# control_pad_v1-1-0x.net
KiCad netlist of a schematic drawn in EAGLE
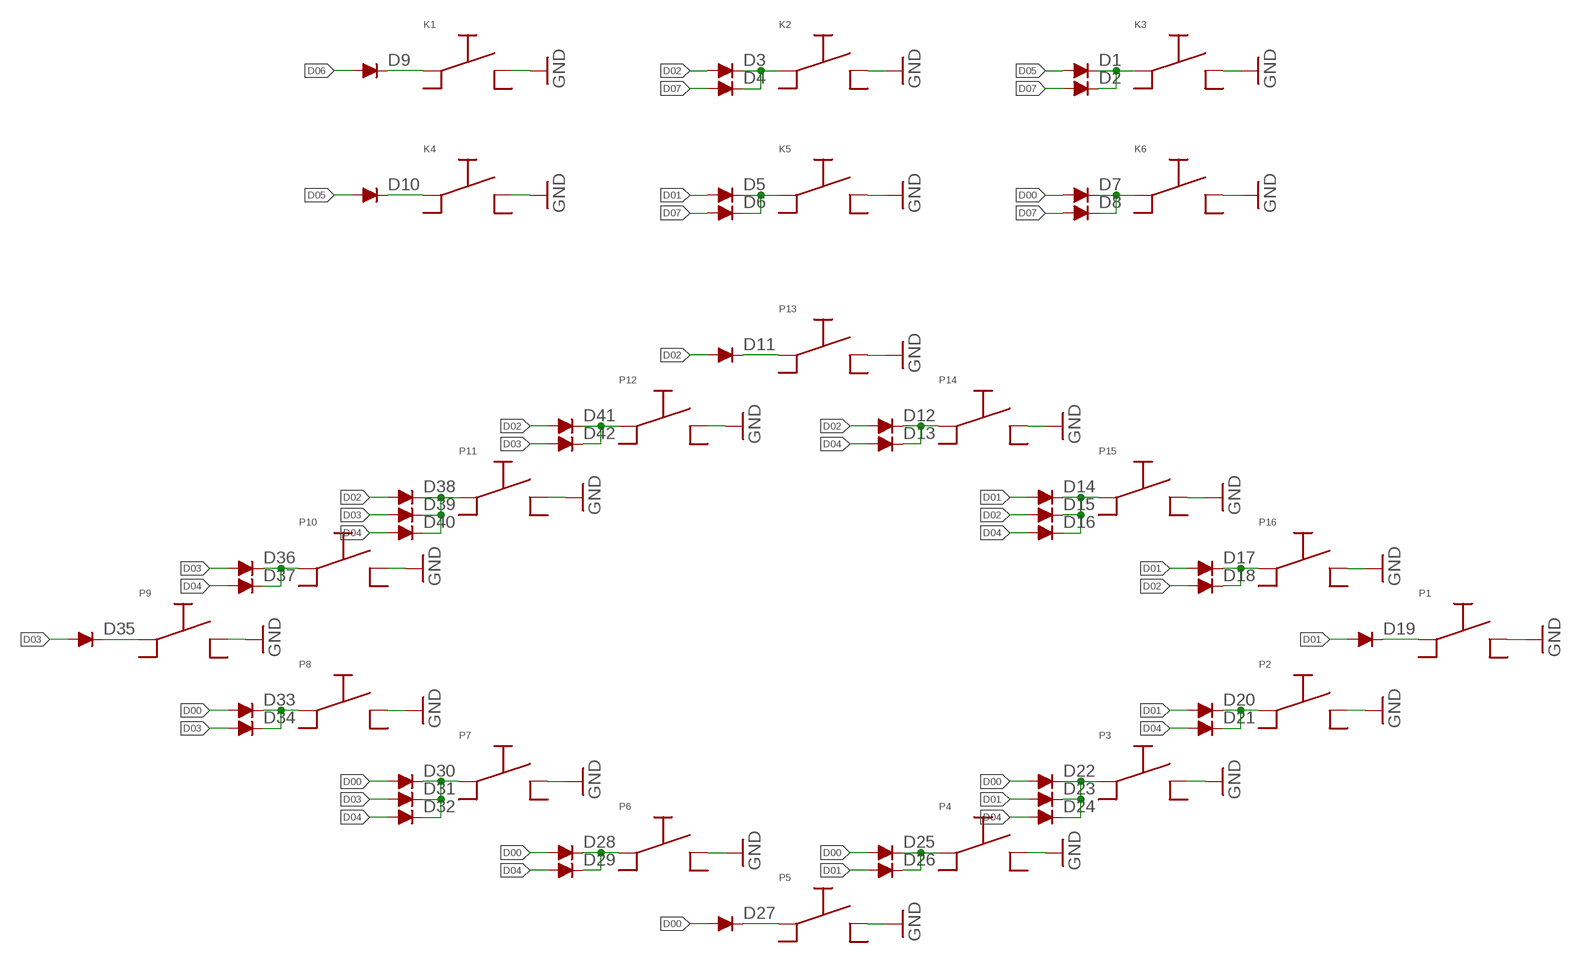
[diagram p0: schematic, sheet 1]

(export (version "E")
  (design (tool "Eeschema 10.0.6"))
  (components
    (comp (ref "D1")
      (value "1N4148")
      (footprint "eagle-import:DO35-10")
      (libsource (lib "eagle-import") (part "1N4148"))
    )
    (comp (ref "D2")
      (value "1N4148")
      (footprint "eagle-import:DO35-10")
      (libsource (lib "eagle-import") (part "1N4148"))
    )
    (comp (ref "D3")
      (value "1N4148")
      (footprint "eagle-import:DO35-10")
      (libsource (lib "eagle-import") (part "1N4148"))
    )
    (comp (ref "D4")
      (value "1N4148")
      (footprint "eagle-import:DO35-10")
      (libsource (lib "eagle-import") (part "1N4148"))
    )
    (comp (ref "D5")
      (value "1N4148")
      (footprint "eagle-import:DO35-10")
      (libsource (lib "eagle-import") (part "1N4148"))
    )
    (comp (ref "D6")
      (value "1N4148")
      (footprint "eagle-import:DO35-10")
      (libsource (lib "eagle-import") (part "1N4148"))
    )
    (comp (ref "D7")
      (value "1N4148")
      (footprint "eagle-import:DO35-10")
      (libsource (lib "eagle-import") (part "1N4148"))
    )
    (comp (ref "D8")
      (value "1N4148")
      (footprint "eagle-import:DO35-10")
      (libsource (lib "eagle-import") (part "1N4148"))
    )
    (comp (ref "D9")
      (value "1N4148")
      (footprint "eagle-import:DO35-10")
      (libsource (lib "eagle-import") (part "1N4148"))
    )
    (comp (ref "D10")
      (value "1N4148")
      (footprint "eagle-import:DO35-10")
      (libsource (lib "eagle-import") (part "1N4148"))
    )
    (comp (ref "D11")
      (value "1N4148")
      (footprint "eagle-import:DO35-10")
      (libsource (lib "eagle-import") (part "1N4148"))
    )
    (comp (ref "D12")
      (value "1N4148")
      (footprint "eagle-import:DO35-10")
      (libsource (lib "eagle-import") (part "1N4148"))
    )
    (comp (ref "D13")
      (value "1N4148")
      (footprint "eagle-import:DO35-10")
      (libsource (lib "eagle-import") (part "1N4148"))
    )
    (comp (ref "D14")
      (value "1N4148")
      (footprint "eagle-import:DO35-10")
      (libsource (lib "eagle-import") (part "1N4148"))
    )
    (comp (ref "D15")
      (value "1N4148")
      (footprint "eagle-import:DO35-10")
      (libsource (lib "eagle-import") (part "1N4148"))
    )
    (comp (ref "D16")
      (value "1N4148")
      (footprint "eagle-import:DO35-10")
      (libsource (lib "eagle-import") (part "1N4148"))
    )
    (comp (ref "D17")
      (value "1N4148")
      (footprint "eagle-import:DO35-10")
      (libsource (lib "eagle-import") (part "1N4148"))
    )
    (comp (ref "D18")
      (value "1N4148")
      (footprint "eagle-import:DO35-10")
      (libsource (lib "eagle-import") (part "1N4148"))
    )
    (comp (ref "D19")
      (value "1N4148")
      (footprint "eagle-import:DO35-10")
      (libsource (lib "eagle-import") (part "1N4148"))
    )
    (comp (ref "D20")
      (value "1N4148")
      (footprint "eagle-import:DO35-10")
      (libsource (lib "eagle-import") (part "1N4148"))
    )
    (comp (ref "D21")
      (value "1N4148")
      (footprint "eagle-import:DO35-10")
      (libsource (lib "eagle-import") (part "1N4148"))
    )
    (comp (ref "D22")
      (value "1N4148")
      (footprint "eagle-import:DO35-10")
      (libsource (lib "eagle-import") (part "1N4148"))
    )
    (comp (ref "D23")
      (value "1N4148")
      (footprint "eagle-import:DO35-10")
      (libsource (lib "eagle-import") (part "1N4148"))
    )
    (comp (ref "D24")
      (value "1N4148")
      (footprint "eagle-import:DO35-10")
      (libsource (lib "eagle-import") (part "1N4148"))
    )
    (comp (ref "D25")
      (value "1N4148")
      (footprint "eagle-import:DO35-10")
      (libsource (lib "eagle-import") (part "1N4148"))
    )
    (comp (ref "D26")
      (value "1N4148")
      (footprint "eagle-import:DO35-10")
      (libsource (lib "eagle-import") (part "1N4148"))
    )
    (comp (ref "D27")
      (value "1N4148")
      (footprint "eagle-import:DO35-10")
      (libsource (lib "eagle-import") (part "1N4148"))
    )
    (comp (ref "D28")
      (value "1N4148")
      (footprint "eagle-import:DO35-10")
      (libsource (lib "eagle-import") (part "1N4148"))
    )
    (comp (ref "D29")
      (value "1N4148")
      (footprint "eagle-import:DO35-10")
      (libsource (lib "eagle-import") (part "1N4148"))
    )
    (comp (ref "D30")
      (value "1N4148")
      (footprint "eagle-import:DO35-10")
      (libsource (lib "eagle-import") (part "1N4148"))
    )
    (comp (ref "D31")
      (value "1N4148")
      (footprint "eagle-import:DO35-10")
      (libsource (lib "eagle-import") (part "1N4148"))
    )
    (comp (ref "D32")
      (value "1N4148")
      (footprint "eagle-import:DO35-10")
      (libsource (lib "eagle-import") (part "1N4148"))
    )
    (comp (ref "D33")
      (value "1N4148")
      (footprint "eagle-import:DO35-10")
      (libsource (lib "eagle-import") (part "1N4148"))
    )
    (comp (ref "D34")
      (value "1N4148")
      (footprint "eagle-import:DO35-10")
      (libsource (lib "eagle-import") (part "1N4148"))
    )
    (comp (ref "D35")
      (value "1N4148")
      (footprint "eagle-import:DO35-10")
      (libsource (lib "eagle-import") (part "1N4148"))
    )
    (comp (ref "D36")
      (value "1N4148")
      (footprint "eagle-import:DO35-10")
      (libsource (lib "eagle-import") (part "1N4148"))
    )
    (comp (ref "D37")
      (value "1N4148")
      (footprint "eagle-import:DO35-10")
      (libsource (lib "eagle-import") (part "1N4148"))
    )
    (comp (ref "D38")
      (value "1N4148")
      (footprint "eagle-import:DO35-10")
      (libsource (lib "eagle-import") (part "1N4148"))
    )
    (comp (ref "D39")
      (value "1N4148")
      (footprint "eagle-import:DO35-10")
      (libsource (lib "eagle-import") (part "1N4148"))
    )
    (comp (ref "D40")
      (value "1N4148")
      (footprint "eagle-import:DO35-10")
      (libsource (lib "eagle-import") (part "1N4148"))
    )
    (comp (ref "D41")
      (value "1N4148")
      (footprint "eagle-import:DO35-10")
      (libsource (lib "eagle-import") (part "1N4148"))
    )
    (comp (ref "D42")
      (value "1N4148")
      (footprint "eagle-import:DO35-10")
      (libsource (lib "eagle-import") (part "1N4148"))
    )
    (comp (ref "K1")
      (value "TACT-SPST")
      (footprint "eagle-import:TACT-SPST")
      (libsource (lib "eagle-import") (part "TACT-SPST"))
    )
    (comp (ref "K2")
      (value "TACT-SPST")
      (footprint "eagle-import:TACT-SPST")
      (libsource (lib "eagle-import") (part "TACT-SPST"))
    )
    (comp (ref "K3")
      (value "TACT-SPST")
      (footprint "eagle-import:TACT-SPST")
      (libsource (lib "eagle-import") (part "TACT-SPST"))
    )
    (comp (ref "K4")
      (value "TACT-SPST")
      (footprint "eagle-import:TACT-SPST")
      (libsource (lib "eagle-import") (part "TACT-SPST"))
    )
    (comp (ref "K5")
      (value "TACT-SPST")
      (footprint "eagle-import:TACT-SPST")
      (libsource (lib "eagle-import") (part "TACT-SPST"))
    )
    (comp (ref "K6")
      (value "TACT-SPST")
      (footprint "eagle-import:TACT-SPST")
      (libsource (lib "eagle-import") (part "TACT-SPST"))
    )
    (comp (ref "P1")
      (value "TACT-SPST")
      (footprint "eagle-import:TACT-SPST")
      (libsource (lib "eagle-import") (part "TACT-SPST"))
    )
    (comp (ref "P2")
      (value "TACT-SPST")
      (footprint "eagle-import:TACT-SPST")
      (libsource (lib "eagle-import") (part "TACT-SPST"))
    )
    (comp (ref "P3")
      (value "TACT-SPST")
      (footprint "eagle-import:TACT-SPST")
      (libsource (lib "eagle-import") (part "TACT-SPST"))
    )
    (comp (ref "P4")
      (value "TACT-SPST")
      (footprint "eagle-import:TACT-SPST")
      (libsource (lib "eagle-import") (part "TACT-SPST"))
    )
    (comp (ref "P5")
      (value "TACT-SPST")
      (footprint "eagle-import:TACT-SPST")
      (libsource (lib "eagle-import") (part "TACT-SPST"))
    )
    (comp (ref "P6")
      (value "TACT-SPST")
      (footprint "eagle-import:TACT-SPST")
      (libsource (lib "eagle-import") (part "TACT-SPST"))
    )
    (comp (ref "P7")
      (value "TACT-SPST")
      (footprint "eagle-import:TACT-SPST")
      (libsource (lib "eagle-import") (part "TACT-SPST"))
    )
    (comp (ref "P8")
      (value "TACT-SPST")
      (footprint "eagle-import:TACT-SPST")
      (libsource (lib "eagle-import") (part "TACT-SPST"))
    )
    (comp (ref "P9")
      (value "TACT-SPST")
      (footprint "eagle-import:TACT-SPST")
      (libsource (lib "eagle-import") (part "TACT-SPST"))
    )
    (comp (ref "P10")
      (value "TACT-SPST")
      (footprint "eagle-import:TACT-SPST")
      (libsource (lib "eagle-import") (part "TACT-SPST"))
    )
    (comp (ref "P11")
      (value "TACT-SPST")
      (footprint "eagle-import:TACT-SPST")
      (libsource (lib "eagle-import") (part "TACT-SPST"))
    )
    (comp (ref "P12")
      (value "TACT-SPST")
      (footprint "eagle-import:TACT-SPST")
      (libsource (lib "eagle-import") (part "TACT-SPST"))
    )
    (comp (ref "P13")
      (value "TACT-SPST")
      (footprint "eagle-import:TACT-SPST")
      (libsource (lib "eagle-import") (part "TACT-SPST"))
    )
    (comp (ref "P14")
      (value "TACT-SPST")
      (footprint "eagle-import:TACT-SPST")
      (libsource (lib "eagle-import") (part "TACT-SPST"))
    )
    (comp (ref "P15")
      (value "TACT-SPST")
      (footprint "eagle-import:TACT-SPST")
      (libsource (lib "eagle-import") (part "TACT-SPST"))
    )
    (comp (ref "P16")
      (value "TACT-SPST")
      (footprint "eagle-import:TACT-SPST")
      (libsource (lib "eagle-import") (part "TACT-SPST"))
    )
  )
  (nets
    (net (code "1") (name "D00") (class "Default")
      (node (ref "D22") (pin "A") (pinfunction "A_A") (pintype "passive"))
      (node (ref "D25") (pin "A") (pinfunction "A_A") (pintype "passive"))
      (node (ref "D27") (pin "A") (pinfunction "A_A") (pintype "passive"))
      (node (ref "D28") (pin "A") (pinfunction "A_A") (pintype "passive"))
      (node (ref "D30") (pin "A") (pinfunction "A_A") (pintype "passive"))
      (node (ref "D33") (pin "A") (pinfunction "A_A") (pintype "passive"))
      (node (ref "D7") (pin "A") (pinfunction "A_A") (pintype "passive"))
    )
    (net (code "2") (name "D01") (class "Default")
      (node (ref "D14") (pin "A") (pinfunction "A_A") (pintype "passive"))
      (node (ref "D17") (pin "A") (pinfunction "A_A") (pintype "passive"))
      (node (ref "D19") (pin "A") (pinfunction "A_A") (pintype "passive"))
      (node (ref "D20") (pin "A") (pinfunction "A_A") (pintype "passive"))
      (node (ref "D23") (pin "A") (pinfunction "A_A") (pintype "passive"))
      (node (ref "D26") (pin "A") (pinfunction "A_A") (pintype "passive"))
      (node (ref "D5") (pin "A") (pinfunction "A_A") (pintype "passive"))
    )
    (net (code "3") (name "D02") (class "Default")
      (node (ref "D11") (pin "A") (pinfunction "A_A") (pintype "passive"))
      (node (ref "D12") (pin "A") (pinfunction "A_A") (pintype "passive"))
      (node (ref "D15") (pin "A") (pinfunction "A_A") (pintype "passive"))
      (node (ref "D18") (pin "A") (pinfunction "A_A") (pintype "passive"))
      (node (ref "D3") (pin "A") (pinfunction "A_A") (pintype "passive"))
      (node (ref "D38") (pin "A") (pinfunction "A_A") (pintype "passive"))
      (node (ref "D41") (pin "A") (pinfunction "A_A") (pintype "passive"))
    )
    (net (code "4") (name "D03") (class "Default")
      (node (ref "D31") (pin "A") (pinfunction "A_A") (pintype "passive"))
      (node (ref "D34") (pin "A") (pinfunction "A_A") (pintype "passive"))
      (node (ref "D35") (pin "A") (pinfunction "A_A") (pintype "passive"))
      (node (ref "D36") (pin "A") (pinfunction "A_A") (pintype "passive"))
      (node (ref "D39") (pin "A") (pinfunction "A_A") (pintype "passive"))
      (node (ref "D42") (pin "A") (pinfunction "A_A") (pintype "passive"))
    )
    (net (code "5") (name "D04") (class "Default")
      (node (ref "D13") (pin "A") (pinfunction "A_A") (pintype "passive"))
      (node (ref "D16") (pin "A") (pinfunction "A_A") (pintype "passive"))
      (node (ref "D21") (pin "A") (pinfunction "A_A") (pintype "passive"))
      (node (ref "D24") (pin "A") (pinfunction "A_A") (pintype "passive"))
      (node (ref "D29") (pin "A") (pinfunction "A_A") (pintype "passive"))
      (node (ref "D32") (pin "A") (pinfunction "A_A") (pintype "passive"))
      (node (ref "D37") (pin "A") (pinfunction "A_A") (pintype "passive"))
      (node (ref "D40") (pin "A") (pinfunction "A_A") (pintype "passive"))
    )
    (net (code "6") (name "D05") (class "Default")
      (node (ref "D1") (pin "A") (pinfunction "A_A") (pintype "passive"))
      (node (ref "D10") (pin "A") (pinfunction "A_A") (pintype "passive"))
    )
    (net (code "7") (name "D06") (class "Default")
      (node (ref "D9") (pin "A") (pinfunction "A_A") (pintype "passive"))
    )
    (net (code "8") (name "D07") (class "Default")
      (node (ref "D2") (pin "A") (pinfunction "A_A") (pintype "passive"))
      (node (ref "D4") (pin "A") (pinfunction "A_A") (pintype "passive"))
      (node (ref "D6") (pin "A") (pinfunction "A_A") (pintype "passive"))
      (node (ref "D8") (pin "A") (pinfunction "A_A") (pintype "passive"))
    )
    (net (code "9") (name "GND") (class "Default")
      (node (ref "K1") (pin "P$2") (pinfunction "P$2_P$2") (pintype "bidirectional"))
      (node (ref "K1") (pin "P$4") (pinfunction "P$2_P$4") (pintype "bidirectional"))
      (node (ref "K2") (pin "P$2") (pinfunction "P$2_P$2") (pintype "bidirectional"))
      (node (ref "K2") (pin "P$4") (pinfunction "P$2_P$4") (pintype "bidirectional"))
      (node (ref "K3") (pin "P$2") (pinfunction "P$2_P$2") (pintype "bidirectional"))
      (node (ref "K3") (pin "P$4") (pinfunction "P$2_P$4") (pintype "bidirectional"))
      (node (ref "K4") (pin "P$2") (pinfunction "P$2_P$2") (pintype "bidirectional"))
      (node (ref "K4") (pin "P$4") (pinfunction "P$2_P$4") (pintype "bidirectional"))
      (node (ref "K5") (pin "P$2") (pinfunction "P$2_P$2") (pintype "bidirectional"))
      (node (ref "K5") (pin "P$4") (pinfunction "P$2_P$4") (pintype "bidirectional"))
      (node (ref "K6") (pin "P$2") (pinfunction "P$2_P$2") (pintype "bidirectional"))
      (node (ref "K6") (pin "P$4") (pinfunction "P$2_P$4") (pintype "bidirectional"))
      (node (ref "P1") (pin "P$2") (pinfunction "P$2_P$2") (pintype "bidirectional"))
      (node (ref "P1") (pin "P$4") (pinfunction "P$2_P$4") (pintype "bidirectional"))
      (node (ref "P10") (pin "P$2") (pinfunction "P$2_P$2") (pintype "bidirectional"))
      (node (ref "P10") (pin "P$4") (pinfunction "P$2_P$4") (pintype "bidirectional"))
      (node (ref "P11") (pin "P$2") (pinfunction "P$2_P$2") (pintype "bidirectional"))
      (node (ref "P11") (pin "P$4") (pinfunction "P$2_P$4") (pintype "bidirectional"))
      (node (ref "P12") (pin "P$2") (pinfunction "P$2_P$2") (pintype "bidirectional"))
      (node (ref "P12") (pin "P$4") (pinfunction "P$2_P$4") (pintype "bidirectional"))
      (node (ref "P13") (pin "P$2") (pinfunction "P$2_P$2") (pintype "bidirectional"))
      (node (ref "P13") (pin "P$4") (pinfunction "P$2_P$4") (pintype "bidirectional"))
      (node (ref "P14") (pin "P$2") (pinfunction "P$2_P$2") (pintype "bidirectional"))
      (node (ref "P14") (pin "P$4") (pinfunction "P$2_P$4") (pintype "bidirectional"))
      (node (ref "P15") (pin "P$2") (pinfunction "P$2_P$2") (pintype "bidirectional"))
      (node (ref "P15") (pin "P$4") (pinfunction "P$2_P$4") (pintype "bidirectional"))
      (node (ref "P16") (pin "P$2") (pinfunction "P$2_P$2") (pintype "bidirectional"))
      (node (ref "P16") (pin "P$4") (pinfunction "P$2_P$4") (pintype "bidirectional"))
      (node (ref "P2") (pin "P$2") (pinfunction "P$2_P$2") (pintype "bidirectional"))
      (node (ref "P2") (pin "P$4") (pinfunction "P$2_P$4") (pintype "bidirectional"))
      (node (ref "P3") (pin "P$2") (pinfunction "P$2_P$2") (pintype "bidirectional"))
      (node (ref "P3") (pin "P$4") (pinfunction "P$2_P$4") (pintype "bidirectional"))
      (node (ref "P4") (pin "P$2") (pinfunction "P$2_P$2") (pintype "bidirectional"))
      (node (ref "P4") (pin "P$4") (pinfunction "P$2_P$4") (pintype "bidirectional"))
      (node (ref "P5") (pin "P$2") (pinfunction "P$2_P$2") (pintype "bidirectional"))
      (node (ref "P5") (pin "P$4") (pinfunction "P$2_P$4") (pintype "bidirectional"))
      (node (ref "P6") (pin "P$2") (pinfunction "P$2_P$2") (pintype "bidirectional"))
      (node (ref "P6") (pin "P$4") (pinfunction "P$2_P$4") (pintype "bidirectional"))
      (node (ref "P7") (pin "P$2") (pinfunction "P$2_P$2") (pintype "bidirectional"))
      (node (ref "P7") (pin "P$4") (pinfunction "P$2_P$4") (pintype "bidirectional"))
      (node (ref "P8") (pin "P$2") (pinfunction "P$2_P$2") (pintype "bidirectional"))
      (node (ref "P8") (pin "P$4") (pinfunction "P$2_P$4") (pintype "bidirectional"))
      (node (ref "P9") (pin "P$2") (pinfunction "P$2_P$2") (pintype "bidirectional"))
      (node (ref "P9") (pin "P$4") (pinfunction "P$2_P$4") (pintype "bidirectional"))
    )
    (net (code "10") (name "Net-(D1-PadC)") (class "Default")
      (node (ref "D1") (pin "C") (pinfunction "C_C") (pintype "passive"))
      (node (ref "D2") (pin "C") (pinfunction "C_C") (pintype "passive"))
      (node (ref "K3") (pin "P$1") (pinfunction "P$1_P$1") (pintype "bidirectional"))
      (node (ref "K3") (pin "P$3") (pinfunction "P$1_P$3") (pintype "bidirectional"))
    )
    (net (code "11") (name "Net-(D3-PadC)") (class "Default")
      (node (ref "D3") (pin "C") (pinfunction "C_C") (pintype "passive"))
      (node (ref "D4") (pin "C") (pinfunction "C_C") (pintype "passive"))
      (node (ref "K2") (pin "P$1") (pinfunction "P$1_P$1") (pintype "bidirectional"))
      (node (ref "K2") (pin "P$3") (pinfunction "P$1_P$3") (pintype "bidirectional"))
    )
    (net (code "12") (name "Net-(D5-PadC)") (class "Default")
      (node (ref "D5") (pin "C") (pinfunction "C_C") (pintype "passive"))
      (node (ref "D6") (pin "C") (pinfunction "C_C") (pintype "passive"))
      (node (ref "K5") (pin "P$1") (pinfunction "P$1_P$1") (pintype "bidirectional"))
      (node (ref "K5") (pin "P$3") (pinfunction "P$1_P$3") (pintype "bidirectional"))
    )
    (net (code "13") (name "Net-(D7-PadC)") (class "Default")
      (node (ref "D7") (pin "C") (pinfunction "C_C") (pintype "passive"))
      (node (ref "D8") (pin "C") (pinfunction "C_C") (pintype "passive"))
      (node (ref "K6") (pin "P$1") (pinfunction "P$1_P$1") (pintype "bidirectional"))
      (node (ref "K6") (pin "P$3") (pinfunction "P$1_P$3") (pintype "bidirectional"))
    )
    (net (code "14") (name "Net-(D9-PadC)") (class "Default")
      (node (ref "D9") (pin "C") (pinfunction "C_C") (pintype "passive"))
      (node (ref "K1") (pin "P$1") (pinfunction "P$1_P$1") (pintype "bidirectional"))
      (node (ref "K1") (pin "P$3") (pinfunction "P$1_P$3") (pintype "bidirectional"))
    )
    (net (code "15") (name "Net-(D10-PadC)") (class "Default")
      (node (ref "D10") (pin "C") (pinfunction "C_C") (pintype "passive"))
      (node (ref "K4") (pin "P$1") (pinfunction "P$1_P$1") (pintype "bidirectional"))
      (node (ref "K4") (pin "P$3") (pinfunction "P$1_P$3") (pintype "bidirectional"))
    )
    (net (code "16") (name "Net-(D11-PadC)") (class "Default")
      (node (ref "D11") (pin "C") (pinfunction "C_C") (pintype "passive"))
      (node (ref "P13") (pin "P$1") (pinfunction "P$1_P$1") (pintype "bidirectional"))
      (node (ref "P13") (pin "P$3") (pinfunction "P$1_P$3") (pintype "bidirectional"))
    )
    (net (code "17") (name "Net-(D12-PadC)") (class "Default")
      (node (ref "D12") (pin "C") (pinfunction "C_C") (pintype "passive"))
      (node (ref "D13") (pin "C") (pinfunction "C_C") (pintype "passive"))
      (node (ref "P14") (pin "P$1") (pinfunction "P$1_P$1") (pintype "bidirectional"))
      (node (ref "P14") (pin "P$3") (pinfunction "P$1_P$3") (pintype "bidirectional"))
    )
    (net (code "18") (name "Net-(D14-PadC)") (class "Default")
      (node (ref "D14") (pin "C") (pinfunction "C_C") (pintype "passive"))
      (node (ref "D15") (pin "C") (pinfunction "C_C") (pintype "passive"))
      (node (ref "D16") (pin "C") (pinfunction "C_C") (pintype "passive"))
      (node (ref "P15") (pin "P$1") (pinfunction "P$1_P$1") (pintype "bidirectional"))
      (node (ref "P15") (pin "P$3") (pinfunction "P$1_P$3") (pintype "bidirectional"))
    )
    (net (code "19") (name "Net-(D17-PadC)") (class "Default")
      (node (ref "D17") (pin "C") (pinfunction "C_C") (pintype "passive"))
      (node (ref "D18") (pin "C") (pinfunction "C_C") (pintype "passive"))
      (node (ref "P16") (pin "P$1") (pinfunction "P$1_P$1") (pintype "bidirectional"))
      (node (ref "P16") (pin "P$3") (pinfunction "P$1_P$3") (pintype "bidirectional"))
    )
    (net (code "20") (name "Net-(D19-PadC)") (class "Default")
      (node (ref "D19") (pin "C") (pinfunction "C_C") (pintype "passive"))
      (node (ref "P1") (pin "P$1") (pinfunction "P$1_P$1") (pintype "bidirectional"))
      (node (ref "P1") (pin "P$3") (pinfunction "P$1_P$3") (pintype "bidirectional"))
    )
    (net (code "21") (name "Net-(D20-PadC)") (class "Default")
      (node (ref "D20") (pin "C") (pinfunction "C_C") (pintype "passive"))
      (node (ref "D21") (pin "C") (pinfunction "C_C") (pintype "passive"))
      (node (ref "P2") (pin "P$1") (pinfunction "P$1_P$1") (pintype "bidirectional"))
      (node (ref "P2") (pin "P$3") (pinfunction "P$1_P$3") (pintype "bidirectional"))
    )
    (net (code "22") (name "Net-(D22-PadC)") (class "Default")
      (node (ref "D22") (pin "C") (pinfunction "C_C") (pintype "passive"))
      (node (ref "D23") (pin "C") (pinfunction "C_C") (pintype "passive"))
      (node (ref "D24") (pin "C") (pinfunction "C_C") (pintype "passive"))
      (node (ref "P3") (pin "P$1") (pinfunction "P$1_P$1") (pintype "bidirectional"))
      (node (ref "P3") (pin "P$3") (pinfunction "P$1_P$3") (pintype "bidirectional"))
    )
    (net (code "23") (name "Net-(D25-PadC)") (class "Default")
      (node (ref "D25") (pin "C") (pinfunction "C_C") (pintype "passive"))
      (node (ref "D26") (pin "C") (pinfunction "C_C") (pintype "passive"))
      (node (ref "P4") (pin "P$1") (pinfunction "P$1_P$1") (pintype "bidirectional"))
      (node (ref "P4") (pin "P$3") (pinfunction "P$1_P$3") (pintype "bidirectional"))
    )
    (net (code "24") (name "Net-(D27-PadC)") (class "Default")
      (node (ref "D27") (pin "C") (pinfunction "C_C") (pintype "passive"))
      (node (ref "P5") (pin "P$1") (pinfunction "P$1_P$1") (pintype "bidirectional"))
      (node (ref "P5") (pin "P$3") (pinfunction "P$1_P$3") (pintype "bidirectional"))
    )
    (net (code "25") (name "Net-(D28-PadC)") (class "Default")
      (node (ref "D28") (pin "C") (pinfunction "C_C") (pintype "passive"))
      (node (ref "D29") (pin "C") (pinfunction "C_C") (pintype "passive"))
      (node (ref "P6") (pin "P$1") (pinfunction "P$1_P$1") (pintype "bidirectional"))
      (node (ref "P6") (pin "P$3") (pinfunction "P$1_P$3") (pintype "bidirectional"))
    )
    (net (code "26") (name "Net-(D30-PadC)") (class "Default")
      (node (ref "D30") (pin "C") (pinfunction "C_C") (pintype "passive"))
      (node (ref "D31") (pin "C") (pinfunction "C_C") (pintype "passive"))
      (node (ref "D32") (pin "C") (pinfunction "C_C") (pintype "passive"))
      (node (ref "P7") (pin "P$1") (pinfunction "P$1_P$1") (pintype "bidirectional"))
      (node (ref "P7") (pin "P$3") (pinfunction "P$1_P$3") (pintype "bidirectional"))
    )
    (net (code "27") (name "Net-(D33-PadC)") (class "Default")
      (node (ref "D33") (pin "C") (pinfunction "C_C") (pintype "passive"))
      (node (ref "D34") (pin "C") (pinfunction "C_C") (pintype "passive"))
      (node (ref "P8") (pin "P$1") (pinfunction "P$1_P$1") (pintype "bidirectional"))
      (node (ref "P8") (pin "P$3") (pinfunction "P$1_P$3") (pintype "bidirectional"))
    )
    (net (code "28") (name "Net-(D35-PadC)") (class "Default")
      (node (ref "D35") (pin "C") (pinfunction "C_C") (pintype "passive"))
      (node (ref "P9") (pin "P$1") (pinfunction "P$1_P$1") (pintype "bidirectional"))
      (node (ref "P9") (pin "P$3") (pinfunction "P$1_P$3") (pintype "bidirectional"))
    )
    (net (code "29") (name "Net-(D36-PadC)") (class "Default")
      (node (ref "D36") (pin "C") (pinfunction "C_C") (pintype "passive"))
      (node (ref "D37") (pin "C") (pinfunction "C_C") (pintype "passive"))
      (node (ref "P10") (pin "P$1") (pinfunction "P$1_P$1") (pintype "bidirectional"))
      (node (ref "P10") (pin "P$3") (pinfunction "P$1_P$3") (pintype "bidirectional"))
    )
    (net (code "30") (name "Net-(D38-PadC)") (class "Default")
      (node (ref "D38") (pin "C") (pinfunction "C_C") (pintype "passive"))
      (node (ref "D39") (pin "C") (pinfunction "C_C") (pintype "passive"))
      (node (ref "D40") (pin "C") (pinfunction "C_C") (pintype "passive"))
      (node (ref "P11") (pin "P$1") (pinfunction "P$1_P$1") (pintype "bidirectional"))
      (node (ref "P11") (pin "P$3") (pinfunction "P$1_P$3") (pintype "bidirectional"))
    )
    (net (code "31") (name "Net-(D41-PadC)") (class "Default")
      (node (ref "D41") (pin "C") (pinfunction "C_C") (pintype "passive"))
      (node (ref "D42") (pin "C") (pinfunction "C_C") (pintype "passive"))
      (node (ref "P12") (pin "P$1") (pinfunction "P$1_P$1") (pintype "bidirectional"))
      (node (ref "P12") (pin "P$3") (pinfunction "P$1_P$3") (pintype "bidirectional"))
    )
  )
)
